# led.net
KiCad netlist of a schematic drawn in EAGLE
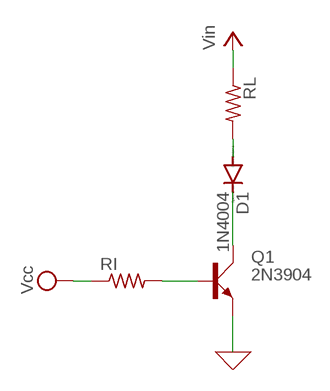
[diagram p0: schematic, sheet 1]

(export (version "E")
  (design (tool "Eeschema 10.0.6"))
  (components
    (comp (ref "D1")
      (value "1N4004")
      (footprint "eagle-import:DO41-10")
      (libsource (lib "eagle-import") (part "1N4004"))
    )
    (comp (ref "Q1")
      (value "2N3904")
      (footprint "eagle-import:TO92D")
      (libsource (lib "eagle-import") (part "2N3904"))
    )
    (comp (ref "RI")
      (value "R-US_0204/7")
      (footprint "eagle-import:0204_7")
      (libsource (lib "eagle-import") (part "R-US_0204/7"))
    )
    (comp (ref "RL")
      (value "R-US_0204/7")
      (footprint "eagle-import:0204_7")
      (libsource (lib "eagle-import") (part "R-US_0204/7"))
    )
  )
  (nets
    (net (code "1") (name "GND") (class "Default")
      (node (ref "Q1") (pin "E") (pinfunction "E_E") (pintype "passive"))
    )
    (net (code "2") (name "Net-(D1-PadA)") (class "Default")
      (node (ref "D1") (pin "A") (pinfunction "A_A") (pintype "passive"))
      (node (ref "RL") (pin "2") (pinfunction "2_2") (pintype "passive"))
    )
    (net (code "3") (name "Net-(D1-PadC)") (class "Default")
      (node (ref "D1") (pin "C") (pinfunction "C_C") (pintype "passive"))
      (node (ref "Q1") (pin "C") (pinfunction "C_C") (pintype "passive"))
    )
    (net (code "4") (name "Net-(Q1-PadB)") (class "Default")
      (node (ref "Q1") (pin "B") (pinfunction "B_B") (pintype "passive"))
      (node (ref "RI") (pin "2") (pinfunction "2_2") (pintype "passive"))
    )
    (net (code "5") (name "Vcc") (class "Default")
      (node (ref "RI") (pin "1") (pinfunction "1_1") (pintype "passive"))
      (node (ref "RL") (pin "1") (pinfunction "1_1") (pintype "passive"))
    )
  )
)
